# Power_5V-1_5A.net
KiCad netlist of a schematic drawn in EAGLE
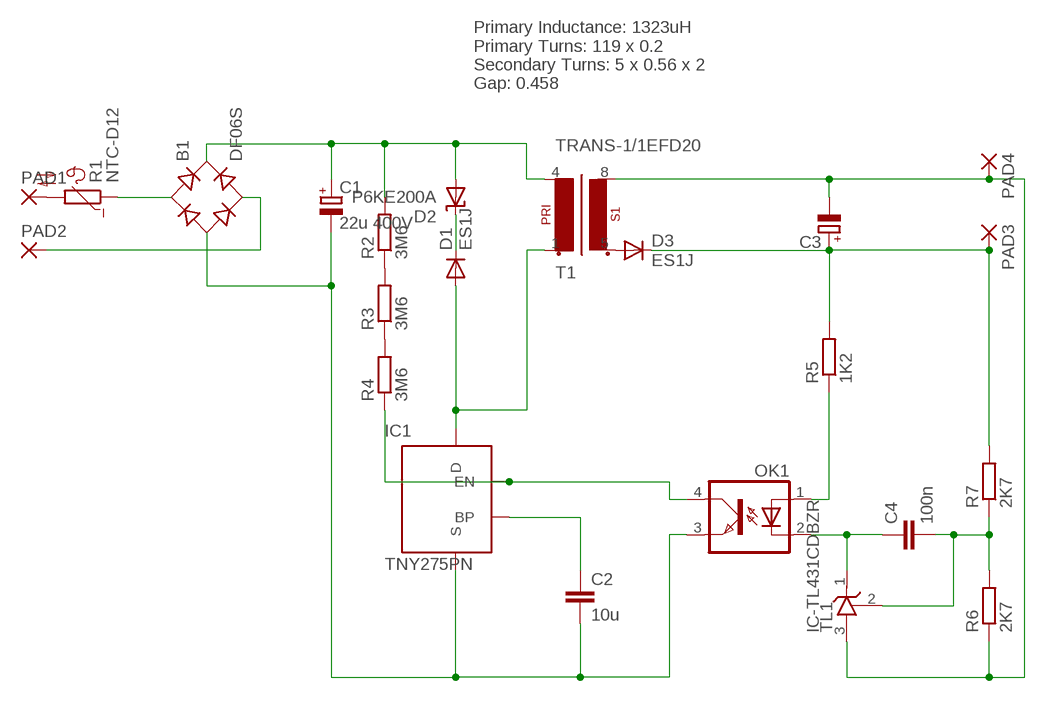
[diagram p0: schematic, sheet 1]

(export (version "E")
  (design (tool "Eeschema 10.0.6"))
  (components
    (comp (ref "B1")
      (value "DF06S")
      (footprint "eagle-import:DFS")
      (libsource (lib "eagle-import") (part "DFS06"))
    )
    (comp (ref "C1")
      (value "22u 400V")
      (footprint "eagle-import:E5-13")
      (libsource (lib "eagle-import") (part "CPOL-EUE5-13"))
    )
    (comp (ref "C2")
      (value "10u")
      (footprint "eagle-import:C1210")
      (libsource (lib "eagle-import") (part "CAP_1210"))
    )
    (comp (ref "C3")
      (value "CPOL-EUE7.5-18")
      (footprint "eagle-import:E7,5-18")
      (libsource (lib "eagle-import") (part "CPOL-EUE7.5-18"))
    )
    (comp (ref "C4")
      (value "100n")
      (footprint "eagle-import:C0805")
      (libsource (lib "eagle-import") (part "CAP_0805"))
    )
    (comp (ref "D1")
      (value "ES1J")
      (footprint "eagle-import:DO214AC")
      (libsource (lib "eagle-import") (part "DIODE_ES1J"))
    )
    (comp (ref "D2")
      (value "P6KE200A")
      (footprint "eagle-import:DO15-12")
      (libsource (lib "eagle-import") (part "SUPRESSORDO-204AC"))
    )
    (comp (ref "D3")
      (value "ES1J")
      (footprint "eagle-import:DO214AC")
      (libsource (lib "eagle-import") (part "DIODE_ES1J"))
    )
    (comp (ref "IC1")
      (value "TNY275PN")
      (footprint "eagle-import:DIP-8C")
      (libsource (lib "eagle-import") (part "POWER-TNY275"))
    )
    (comp (ref "OK1")
      (value "OPTOTRANSPC817")
      (footprint "eagle-import:DIL04")
      (fields (field (name "MPN") "PC817X4J000F"))
      (libsource (lib "eagle-import") (part "OPTOTRANSPC817"))
    )
    (comp (ref "PAD1")
      (value "SMD5")
      (footprint "eagle-import:SMD2,54-5,08")
      (libsource (lib "eagle-import") (part "SMD5"))
    )
    (comp (ref "PAD2")
      (value "SMD5")
      (footprint "eagle-import:SMD2,54-5,08")
      (libsource (lib "eagle-import") (part "SMD5"))
    )
    (comp (ref "PAD3")
      (value "SMD5")
      (footprint "eagle-import:SMD2,54-5,08")
      (libsource (lib "eagle-import") (part "SMD5"))
    )
    (comp (ref "PAD4")
      (value "SMD5")
      (footprint "eagle-import:SMD2,54-5,08")
      (libsource (lib "eagle-import") (part "SMD5"))
    )
    (comp (ref "R1")
      (value "NTC-D12")
      (footprint "eagle-import:NTC-D12")
      (libsource (lib "eagle-import") (part "NTC-D12"))
    )
    (comp (ref "R2")
      (value "3M6")
      (footprint "eagle-import:R0805")
      (libsource (lib "eagle-import") (part "R_0805"))
    )
    (comp (ref "R3")
      (value "3M6")
      (footprint "eagle-import:R0805")
      (libsource (lib "eagle-import") (part "R_0805"))
    )
    (comp (ref "R4")
      (value "3M6")
      (footprint "eagle-import:R0805")
      (libsource (lib "eagle-import") (part "R_0805"))
    )
    (comp (ref "R5")
      (value "1K2")
      (footprint "eagle-import:R1206")
      (libsource (lib "eagle-import") (part "R_1206"))
    )
    (comp (ref "R6")
      (value "2K7")
      (footprint "eagle-import:R1206")
      (libsource (lib "eagle-import") (part "R_1206"))
    )
    (comp (ref "R7")
      (value "2K7")
      (footprint "eagle-import:R1206")
      (libsource (lib "eagle-import") (part "R_1206"))
    )
    (comp (ref "T1")
      (value "TRANS-1/1EFD20")
      (footprint "eagle-import:EFD20_8PIN")
      (libsource (lib "eagle-import") (part "TRANS-1/1EFD20"))
    )
    (comp (ref "TL1")
      (value "IC-TL431CDBZR")
      (footprint "eagle-import:SOT23")
      (libsource (lib "eagle-import") (part "IC-TL431CDBZR"))
    )
  )
  (nets
    (net (code "1") (name "Net-(B1-PadAC1)") (class "Default")
      (node (ref "B1") (pin "AC1") (pinfunction "AC1_AC1") (pintype "passive"))
      (node (ref "R1") (pin "1") (pinfunction "1_1") (pintype "passive"))
    )
    (net (code "2") (name "Net-(D1-PadC)") (class "Default")
      (node (ref "D1") (pin "C") (pinfunction "C_C") (pintype "passive"))
      (node (ref "D2") (pin "C") (pinfunction "C_C") (pintype "passive"))
    )
    (net (code "3") (name "Net-(IC1-BP)") (class "Default")
      (node (ref "C2") (pin "1") (pinfunction "1_1") (pintype "passive"))
      (node (ref "IC1") (pin "2") (pinfunction "BP_2") (pintype "input"))
    )
    (net (code "4") (name "Net-(IC1-D)") (class "Default")
      (node (ref "D1") (pin "A") (pinfunction "A_A") (pintype "passive"))
      (node (ref "IC1") (pin "4") (pinfunction "D_4") (pintype "input"))
      (node (ref "T1") (pin "1") (pinfunction "P1-1_1") (pintype "passive"))
    )
    (net (code "5") (name "Net-(IC1-EN)") (class "Default")
      (node (ref "IC1") (pin "1") (pinfunction "EN_1") (pintype "input"))
      (node (ref "OK1") (pin "4") (pinfunction "COL_4") (pintype "passive"))
      (node (ref "R4") (pin "1") (pinfunction "1_1") (pintype "passive"))
    )
    (net (code "6") (name "Net-(OK1-A)") (class "Default")
      (node (ref "OK1") (pin "1") (pinfunction "A_1") (pintype "passive"))
      (node (ref "R5") (pin "1") (pinfunction "1_1") (pintype "passive"))
    )
    (net (code "7") (name "Net-(OK1-C)") (class "Default")
      (node (ref "C4") (pin "1") (pinfunction "1_1") (pintype "passive"))
      (node (ref "OK1") (pin "2") (pinfunction "C_2") (pintype "passive"))
      (node (ref "TL1") (pin "1") (pinfunction "C_1") (pintype "passive"))
    )
    (net (code "8") (name "Net-(OK1-EMIT)") (class "Default")
      (node (ref "B1") (pin "-") (pinfunction "-_-") (pintype "passive"))
      (node (ref "C1") (pin "-") (pinfunction "-_-") (pintype "passive"))
      (node (ref "C2") (pin "2") (pinfunction "2_2") (pintype "passive"))
      (node (ref "IC1") (pin "5") (pinfunction "S_5") (pintype "input"))
      (node (ref "IC1") (pin "6") (pinfunction "S_6") (pintype "input"))
      (node (ref "IC1") (pin "7") (pinfunction "S_7") (pintype "input"))
      (node (ref "IC1") (pin "8") (pinfunction "S_8") (pintype "input"))
      (node (ref "OK1") (pin "3") (pinfunction "EMIT_3") (pintype "passive"))
    )
    (net (code "9") (name "Net-(PAD1-P)") (class "Default")
      (node (ref "PAD1") (pin "1") (pinfunction "P_1") (pintype "passive"))
      (node (ref "R1") (pin "2") (pinfunction "2_2") (pintype "passive"))
    )
    (net (code "10") (name "Net-(PAD2-P)") (class "Default")
      (node (ref "B1") (pin "AC2") (pinfunction "AC2_AC2") (pintype "passive"))
      (node (ref "PAD2") (pin "1") (pinfunction "P_1") (pintype "passive"))
    )
    (net (code "11") (name "Net-(PAD3-P)") (class "Default")
      (node (ref "C3") (pin "+") (pinfunction "+_+") (pintype "passive"))
      (node (ref "D3") (pin "C") (pinfunction "C_C") (pintype "passive"))
      (node (ref "PAD3") (pin "1") (pinfunction "P_1") (pintype "passive"))
      (node (ref "R5") (pin "2") (pinfunction "2_2") (pintype "passive"))
      (node (ref "R7") (pin "2") (pinfunction "2_2") (pintype "passive"))
    )
    (net (code "12") (name "Net-(PAD4-P)") (class "Default")
      (node (ref "C3") (pin "-") (pinfunction "-_-") (pintype "passive"))
      (node (ref "PAD4") (pin "1") (pinfunction "P_1") (pintype "passive"))
      (node (ref "R6") (pin "1") (pinfunction "1_1") (pintype "passive"))
      (node (ref "T1") (pin "8") (pinfunction "S1-2_8") (pintype "passive"))
      (node (ref "TL1") (pin "3") (pinfunction "A_3") (pintype "passive"))
    )
    (net (code "13") (name "Net-(R2-Pad1)") (class "Default")
      (node (ref "R2") (pin "1") (pinfunction "1_1") (pintype "passive"))
      (node (ref "R3") (pin "2") (pinfunction "2_2") (pintype "passive"))
    )
    (net (code "14") (name "Net-(R3-Pad1)") (class "Default")
      (node (ref "R3") (pin "1") (pinfunction "1_1") (pintype "passive"))
      (node (ref "R4") (pin "2") (pinfunction "2_2") (pintype "passive"))
    )
    (net (code "15") (name "Net-(T1-P1-2)") (class "Default")
      (node (ref "B1") (pin "+") (pinfunction "+_+") (pintype "passive"))
      (node (ref "C1") (pin "+") (pinfunction "+_+") (pintype "passive"))
      (node (ref "D2") (pin "A") (pinfunction "A_A") (pintype "passive"))
      (node (ref "R2") (pin "2") (pinfunction "2_2") (pintype "passive"))
      (node (ref "T1") (pin "4") (pinfunction "P1-2_4") (pintype "passive"))
    )
    (net (code "16") (name "Net-(T1-S1-1)") (class "Default")
      (node (ref "D3") (pin "A") (pinfunction "A_A") (pintype "passive"))
      (node (ref "T1") (pin "5") (pinfunction "S1-1_5") (pintype "passive"))
    )
    (net (code "17") (name "Net-(TL1-R)") (class "Default")
      (node (ref "C4") (pin "2") (pinfunction "2_2") (pintype "passive"))
      (node (ref "R6") (pin "2") (pinfunction "2_2") (pintype "passive"))
      (node (ref "R7") (pin "1") (pinfunction "1_1") (pintype "passive"))
      (node (ref "TL1") (pin "2") (pinfunction "R_2") (pintype "passive"))
    )
  )
)
